# 19-EEPROM_PRESENCE_DETECTION_TEMP_SENSOR.net
KiCad netlist of a schematic drawn in Altium Designer
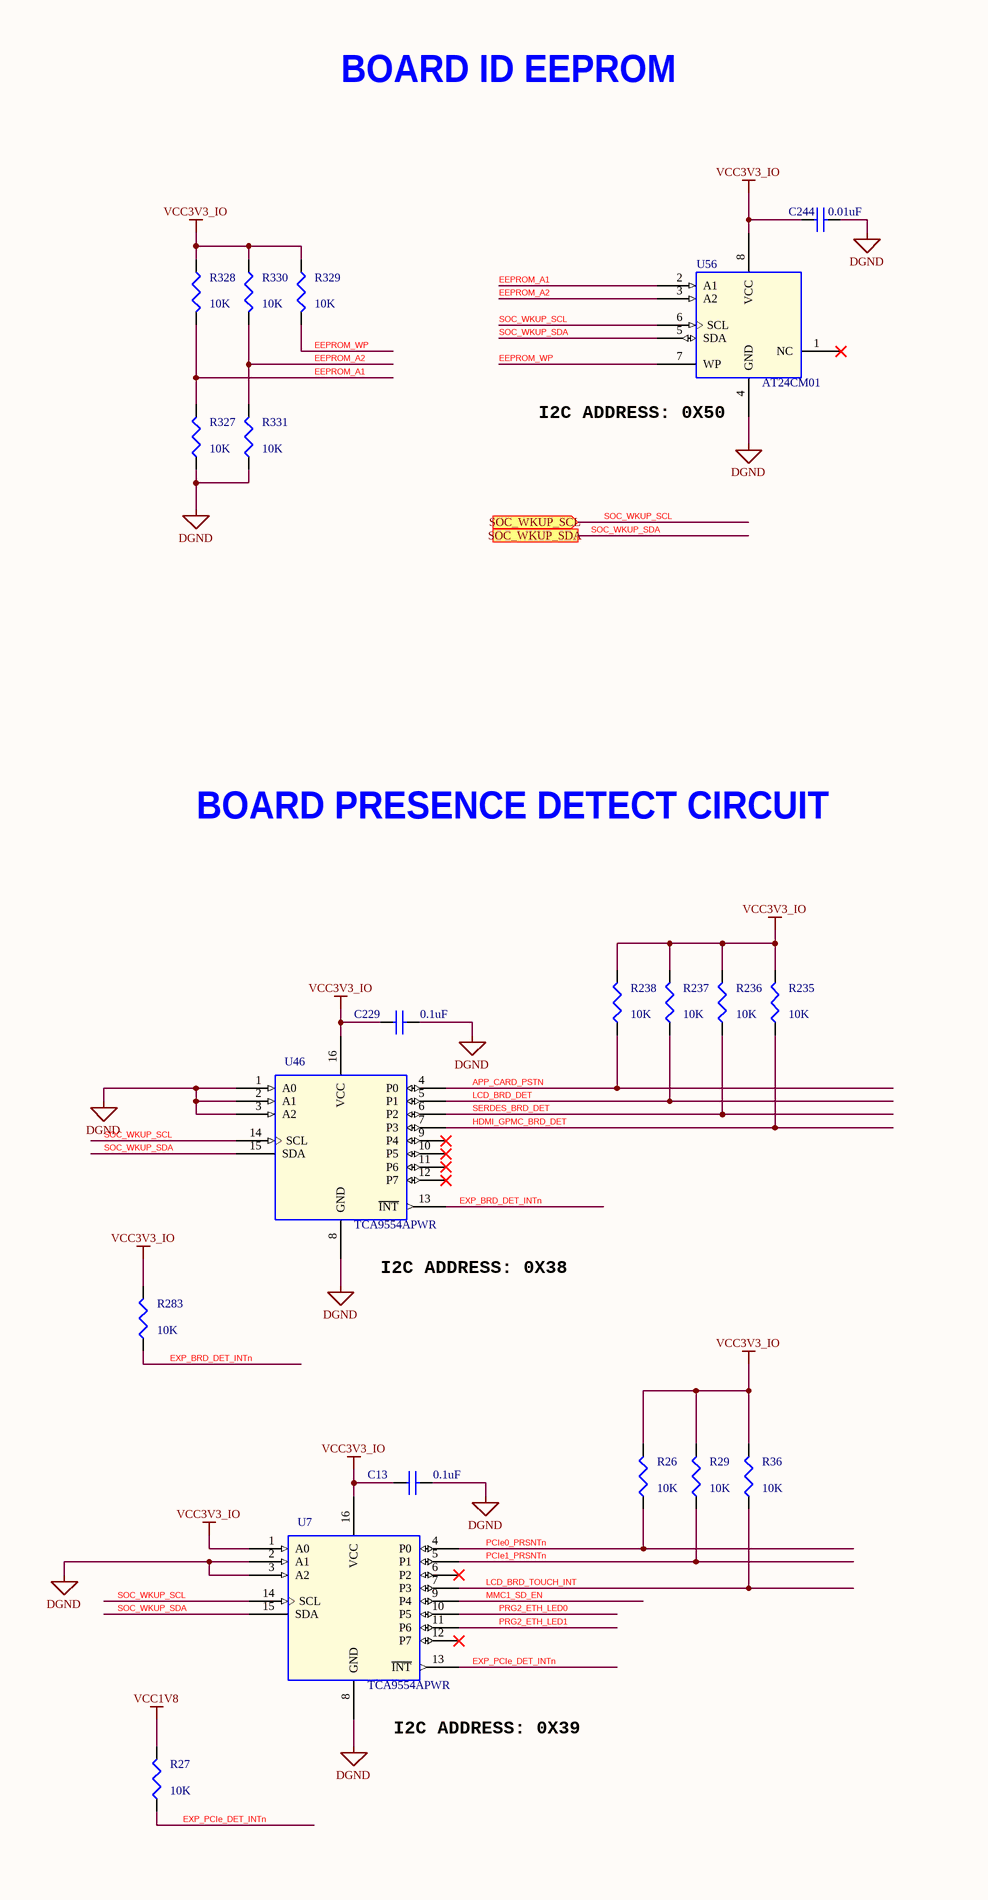
[diagram p0: 19-EEPROM,PRESENCE DETECTION & TEMP SENSOR.SchDoc, left]
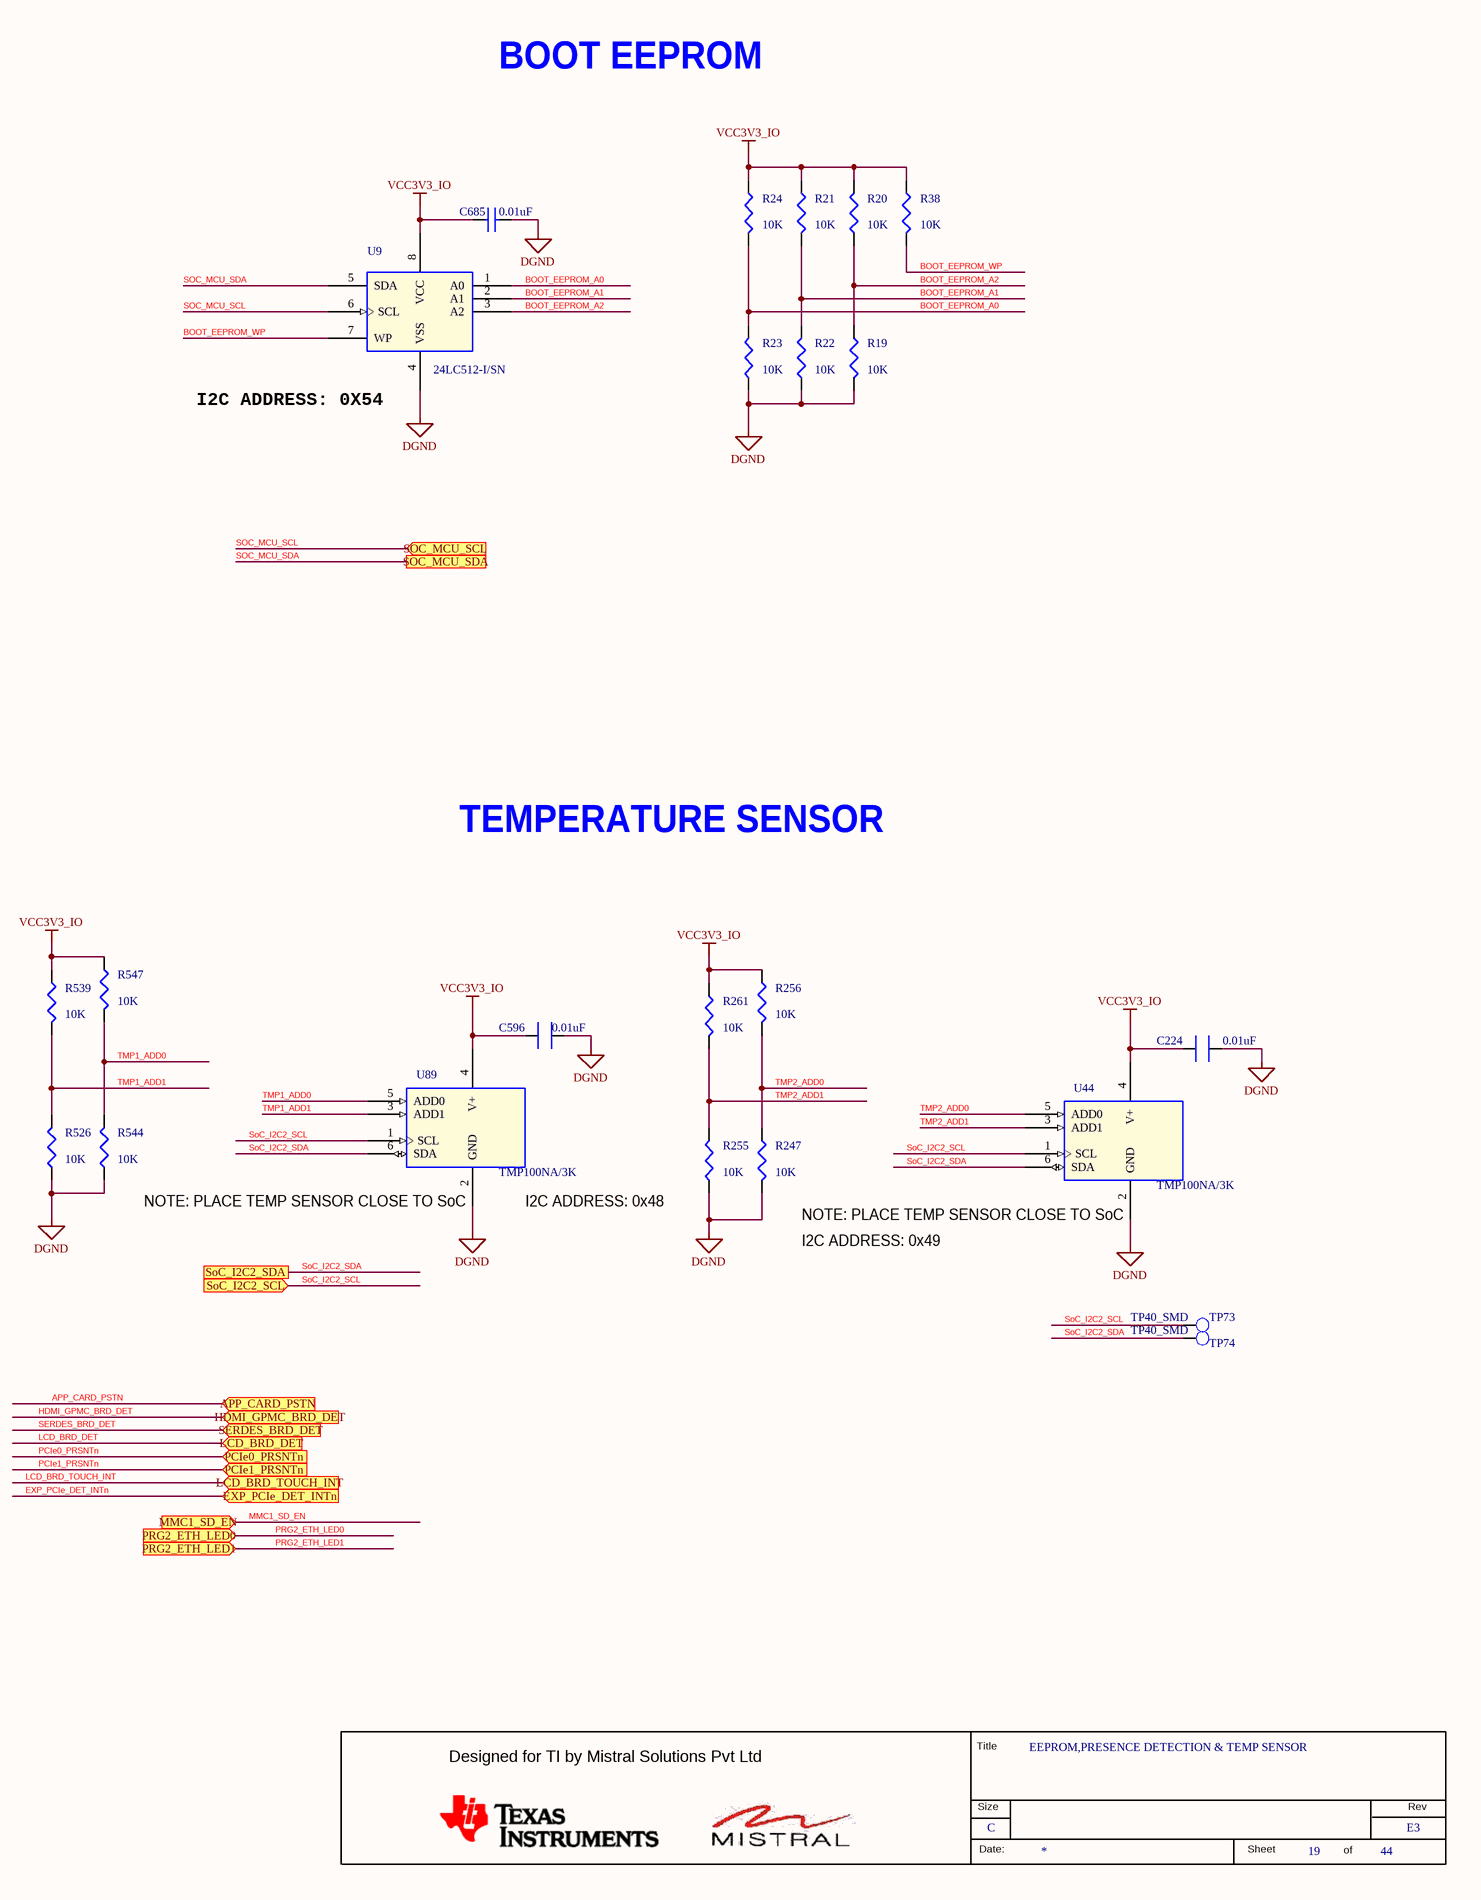
[diagram p1: 19-EEPROM,PRESENCE DETECTION & TEMP SENSOR.SchDoc, right]

(export (version "E")
  (design (tool "Eeschema 10.0.6"))
  (components
    (comp (ref "C13")
      (value "0.1uF")
      (footprint "CAP0201_0-5")
      (description "CAP CERAMIC 0.1uF 16V 10% X5R 0201")
      (fields (field (name "DISTRIBUTOR_PART_NUMBER") "490-16742-1-ND") (field (name "VOLTAGE") "16V"))
      (libsource (lib "*") (part "CAP_Dup5"))
    )
    (comp (ref "C224")
      (value "0.01uF")
      (footprint "TMDX654GPEVM_BRD:CAP0201_0-5")
      (description "CAP CERAMIC 0.01uF 25V 10% X5R 0201")
      (fields
        (field (name "MISTRAL PART NO") "120018010007-R")
        (field (name "MFR_PART_NUMBER") "GRM033R61E103KA12J")
      )
      (libsource (lib "*") (part "CAP_Dup3"))
    )
    (comp (ref "C229")
      (value "0.1uF")
      (footprint "CAP0201_0-5")
      (description "CAP CERAMIC 0.1uF 16V 10% X5R 0201")
      (fields (field (name "DISTRIBUTOR_PART_NUMBER") "490-16742-1-ND") (field (name "VOLTAGE") "16V"))
      (libsource (lib "*") (part "CAP_Dup5"))
    )
    (comp (ref "C244")
      (value "0.01uF")
      (footprint "CAP0201_0-5")
      (description "CAP CERAMIC 0.01uF 25V 10% X5R 0201")
      (fields
        (field (name "MISTRAL PART NO") "120018010007-R")
        (field (name "MFR_PART_NUMBER") "GRM033R61E103KA12J")
      )
      (libsource (lib "*") (part "CAP_Dup5"))
    )
    (comp (ref "C596")
      (value "0.01uF")
      (footprint "TMDX654GPEVM_BRD:CAP0201_0-5")
      (description "CAP CERAMIC 0.01uF 25V 10% X5R 0201")
      (fields
        (field (name "MISTRAL PART NO") "120018010007-R")
        (field (name "MFR_PART_NUMBER") "GRM033R61E103KA12J")
      )
      (libsource (lib "*") (part "CAP_Dup3"))
    )
    (comp (ref "C685")
      (value "0.01uF")
      (footprint "CAP0201_0-5")
      (description "CAP CERAMIC 0.01uF 25V 10% X5R 0201")
      (fields
        (field (name "MISTRAL PART NO") "120018010007-R")
        (field (name "MFR_PART_NUMBER") "GRM033R61E103KA12J")
      )
      (libsource (lib "*") (part "CAP_Dup5"))
    )
    (comp (ref "R19")
      (value "10K")
      (footprint "RES0402_0-5")
      (description "RES 10K 1/16W 5% 0402")
      (fields
        (field (name "MISTRAL PART NO") "110009030208-R")
        (field (name "MFR_PART_NUMBER") "RC0402JR-0710KL")
      )
      (libsource (lib "*") (part "RESISTOR_Dup5"))
    )
    (comp (ref "R20")
      (value "10K")
      (footprint "RES0402_0-5")
      (description "RES 10K 1/16W 5% 0402")
      (fields (field (name "DISTRIBUTOR_PART_NUMBER") "311-10KJRCT-ND") (field (name "VOLTAGE") "NA"))
      (libsource (lib "*") (part "RESISTOR_Dup5"))
    )
    (comp (ref "R21")
      (value "10K")
      (footprint "RES0402_0-5")
      (description "RES 10K 1/16W 5% 0402")
      (fields (field (name "DISTRIBUTOR_PART_NUMBER") "311-10KJRCT-ND") (field (name "VOLTAGE") "NA"))
      (libsource (lib "*") (part "RESISTOR_Dup5"))
    )
    (comp (ref "R22")
      (value "10K")
      (footprint "RES0402_0-5")
      (description "RES 10K 1/16W 5% 0402")
      (fields
        (field (name "MISTRAL PART NO") "110009030208-R")
        (field (name "MFR_PART_NUMBER") "RC0402JR-0710KL")
      )
      (libsource (lib "*") (part "RESISTOR_Dup5"))
    )
    (comp (ref "R23")
      (value "10K")
      (footprint "RES0402_0-5")
      (description "RES 10K 1/16W 5% 0402")
      (fields (field (name "DISTRIBUTOR_PART_NUMBER") "311-10KJRCT-ND") (field (name "VOLTAGE") "NA"))
      (libsource (lib "*") (part "RESISTOR_Dup5"))
    )
    (comp (ref "R24")
      (value "10K")
      (footprint "RES0402_0-5")
      (description "RES 10K 1/16W 5% 0402")
      (fields
        (field (name "MISTRAL PART NO") "110009030208-R")
        (field (name "MFR_PART_NUMBER") "RC0402JR-0710KL")
      )
      (libsource (lib "*") (part "RESISTOR_Dup5"))
    )
    (comp (ref "R26")
      (value "10K")
      (footprint "RES0402_0-5")
      (description "RES 10K 1/16W 5% 0402")
      (fields (field (name "DISTRIBUTOR_PART_NUMBER") "311-10KJRCT-ND") (field (name "VOLTAGE") "NA"))
      (libsource (lib "*") (part "RESISTOR_Dup5"))
    )
    (comp (ref "R27")
      (value "10K")
      (footprint "RES0402_0-5")
      (description "RES 10K 1/16W 5% 0402")
      (fields
        (field (name "MISTRAL PART NO") "110009030208-R")
        (field (name "MFR_PART_NUMBER") "RC0402JR-0710KL")
      )
      (libsource (lib "*") (part "RESISTOR_Dup5"))
    )
    (comp (ref "R29")
      (value "10K")
      (footprint "RES0402_0-5")
      (description "RES 10K 1/16W 5% 0402")
      (fields
        (field (name "MISTRAL PART NO") "110009030208-R")
        (field (name "MFR_PART_NUMBER") "RC0402JR-0710KL")
      )
      (libsource (lib "*") (part "RESISTOR_Dup5"))
    )
    (comp (ref "R36")
      (value "10K")
      (footprint "RES0402_0-5")
      (description "RES 10K 1/16W 5% 0402")
      (fields
        (field (name "MISTRAL PART NO") "110009030208-R")
        (field (name "MFR_PART_NUMBER") "RC0402JR-0710KL")
      )
      (libsource (lib "*") (part "RESISTOR_Dup5"))
    )
    (comp (ref "R38")
      (value "10K")
      (footprint "RES0402_0-5")
      (description "RES 10K 1/16W 5% 0402")
      (fields (field (name "DISTRIBUTOR_PART_NUMBER") "311-10KJRCT-ND") (field (name "VOLTAGE") "NA"))
      (libsource (lib "*") (part "RESISTOR_Dup5"))
    )
    (comp (ref "R235")
      (value "10K")
      (footprint "RES0402_0-5")
      (description "RES 10K 1/16W 5% 0402")
      (fields
        (field (name "MISTRAL PART NO") "110009030208-R")
        (field (name "MFR_PART_NUMBER") "RC0402JR-0710KL")
      )
      (libsource (lib "*") (part "RESISTOR_Dup5"))
    )
    (comp (ref "R236")
      (value "10K")
      (footprint "RES0402_0-5")
      (description "RES 10K 1/16W 5% 0402")
      (fields (field (name "DISTRIBUTOR_PART_NUMBER") "311-10KJRCT-ND") (field (name "VOLTAGE") "NA"))
      (libsource (lib "*") (part "RESISTOR_Dup5"))
    )
    (comp (ref "R237")
      (value "10K")
      (footprint "RES0402_0-5")
      (description "RES 10K 1/16W 5% 0402")
      (fields
        (field (name "MISTRAL PART NO") "110009030208-R")
        (field (name "MFR_PART_NUMBER") "RC0402JR-0710KL")
      )
      (libsource (lib "*") (part "RESISTOR_Dup5"))
    )
    (comp (ref "R238")
      (value "10K")
      (footprint "RES0402_0-5")
      (description "RES 10K 1/16W 5% 0402")
      (fields (field (name "DISTRIBUTOR_PART_NUMBER") "311-10KJRCT-ND") (field (name "VOLTAGE") "NA"))
      (libsource (lib "*") (part "RESISTOR_Dup5"))
    )
    (comp (ref "R247")
      (value "10K")
      (footprint "RES0402_0-5")
      (description "RES 10K 1/16W 5% 0402")
      (fields
        (field (name "MISTRAL PART NO") "110009030208-R")
        (field (name "MFR_PART_NUMBER") "RC0402JR-0710KL")
      )
      (libsource (lib "*") (part "RESISTOR_Dup5"))
    )
    (comp (ref "R255")
      (value "10K")
      (footprint "RES0402_0-5")
      (description "RES 10K 1/16W 5% 0402")
      (fields
        (field (name "MISTRAL PART NO") "110009030208-R")
        (field (name "MFR_PART_NUMBER") "RC0402JR-0710KL")
      )
      (libsource (lib "*") (part "RESISTOR_Dup5"))
    )
    (comp (ref "R256")
      (value "10K")
      (footprint "RES0402_0-5")
      (description "RES 10K 1/16W 5% 0402")
      (fields (field (name "DISTRIBUTOR_PART_NUMBER") "311-10KJRCT-ND") (field (name "VOLTAGE") "NA"))
      (libsource (lib "*") (part "RESISTOR_Dup5"))
    )
    (comp (ref "R261")
      (value "10K")
      (footprint "RES0402_0-5")
      (description "RES 10K 1/16W 5% 0402")
      (fields (field (name "DISTRIBUTOR_PART_NUMBER") "311-10KJRCT-ND") (field (name "VOLTAGE") "NA"))
      (libsource (lib "*") (part "RESISTOR_Dup5"))
    )
    (comp (ref "R283")
      (value "10K")
      (footprint "RES0402_0-5")
      (description "RES 10K 1/16W 5% 0402")
      (fields
        (field (name "MISTRAL PART NO") "110009030208-R")
        (field (name "MFR_PART_NUMBER") "RC0402JR-0710KL")
      )
      (libsource (lib "*") (part "RESISTOR_Dup5"))
    )
    (comp (ref "R327")
      (value "10K")
      (footprint "RES0402_0-5")
      (description "RES 10K 1/16W 5% 0402")
      (fields
        (field (name "MISTRAL PART NO") "110009030208-R")
        (field (name "MFR_PART_NUMBER") "RC0402JR-0710KL")
      )
      (libsource (lib "*") (part "RESISTOR_Dup5"))
    )
    (comp (ref "R328")
      (value "10K")
      (footprint "RES0402_0-5")
      (description "RES 10K 1/16W 5% 0402")
      (fields (field (name "DISTRIBUTOR_PART_NUMBER") "311-10KJRCT-ND") (field (name "VOLTAGE") "NA"))
      (libsource (lib "*") (part "RESISTOR_Dup5"))
    )
    (comp (ref "R329")
      (value "10K")
      (footprint "RES0402_0-5")
      (description "RES 10K 1/16W 5% 0402")
      (fields (field (name "DISTRIBUTOR_PART_NUMBER") "311-10KJRCT-ND") (field (name "VOLTAGE") "NA"))
      (libsource (lib "*") (part "RESISTOR_Dup5"))
    )
    (comp (ref "R330")
      (value "10K")
      (footprint "RES0402_0-5")
      (description "RES 10K 1/16W 5% 0402")
      (fields
        (field (name "MISTRAL PART NO") "110009030208-R")
        (field (name "MFR_PART_NUMBER") "RC0402JR-0710KL")
      )
      (libsource (lib "*") (part "RESISTOR_Dup5"))
    )
    (comp (ref "R331")
      (value "10K")
      (footprint "RES0402_0-5")
      (description "RES 10K 1/16W 5% 0402")
      (fields (field (name "DISTRIBUTOR_PART_NUMBER") "311-10KJRCT-ND") (field (name "VOLTAGE") "NA"))
      (libsource (lib "*") (part "RESISTOR_Dup5"))
    )
    (comp (ref "R526")
      (value "10K")
      (footprint "RES0402_0-5")
      (description "RES 10K 1/16W 5% 0402")
      (fields (field (name "DISTRIBUTOR_PART_NUMBER") "311-10KJRCT-ND") (field (name "VOLTAGE") "NA"))
      (libsource (lib "*") (part "RESISTOR_Dup5"))
    )
    (comp (ref "R539")
      (value "10K")
      (footprint "RES0402_0-5")
      (description "RES 10K 1/16W 5% 0402")
      (fields
        (field (name "MISTRAL PART NO") "110009030208-R")
        (field (name "MFR_PART_NUMBER") "RC0402JR-0710KL")
      )
      (libsource (lib "*") (part "RESISTOR_Dup5"))
    )
    (comp (ref "R544")
      (value "10K")
      (footprint "RES0402_0-5")
      (description "RES 10K 1/16W 5% 0402")
      (fields
        (field (name "MISTRAL PART NO") "110009030208-R")
        (field (name "MFR_PART_NUMBER") "RC0402JR-0710KL")
      )
      (libsource (lib "*") (part "RESISTOR_Dup5"))
    )
    (comp (ref "R547")
      (value "10K")
      (footprint "RES0402_0-5")
      (description "RES 10K 1/16W 5% 0402")
      (fields
        (field (name "MISTRAL PART NO") "110009030208-R")
        (field (name "MFR_PART_NUMBER") "RC0402JR-0710KL")
      )
      (libsource (lib "*") (part "RESISTOR_Dup5"))
    )
    (comp (ref "TP73")
      (value "TP40_SMD")
      (footprint "TP40_SMD")
      (description "TESTPOINT CIR 40 SMD")
      (fields (field (name "VOLTAGE") "NA") (field (name "MISTRAL PART NO") "130009030933"))
      (libsource (lib "*") (part "TESTPOINT"))
    )
    (comp (ref "TP74")
      (value "TP40_SMD")
      (footprint "TP40_SMD")
      (description "TESTPOINT CIR 40 SMD")
      (fields (field (name "MISTRAL PART NO") "130009030933") (field (name "DISTRIBUTOR_PART_NUMBER") "NA"))
      (libsource (lib "*") (part "TESTPOINT"))
    )
    (comp (ref "U7")
      (value "TCA9554APWR")
      (footprint "TSSOP16_25-59_205X180_1-2")
      (description "IC 8-BIT I2C AND SMBUS I/O EXPANDER WITH INTERRUPT O/P TSSOP16")
      (fields (field (name "MISTRAL PART NO") "141017090007-R") (field (name "TOLERANCE") "NA"))
      (libsource (lib "*") (part "TCA9554APWR_TSSOP16"))
    )
    (comp (ref "U9")
      (value "24LC512-I/SN")
      (footprint "SOIC8_1-8")
      (description "IC 512K I2C SERIAL EEPROM MEMORY SOIC8")
      (fields (field (name "MISTRAL PART NO") "141117080005-R") (field (name "TOLERANCE") "NA"))
      (libsource (lib "*") (part "24LC512-ESN_SOIC8"))
    )
    (comp (ref "U44")
      (value "TMP100NA/3K")
      (footprint "SOT23-6_1-5")
      (description "IC TEMPERATURE SENSOR WITH I2C AND SMBUS INTERFACE SOT23-6")
      (fields (field (name "DISTRIBUTOR_PART_NUMBER") "296-26833-1-ND") (field (name "VOLTAGE") "NA"))
      (libsource (lib "*") (part "TMP100NA/3K_SOT23-6"))
    )
    (comp (ref "U46")
      (value "TCA9554APWR")
      (footprint "TSSOP16_25-59_205X180_1-2")
      (description "IC 8-BIT I2C AND SMBUS I/O EXPANDER WITH INTERRUPT O/P TSSOP16")
      (fields (field (name "MISTRAL PART NO") "141017090007-R") (field (name "TOLERANCE") "NA"))
      (libsource (lib "*") (part "TCA9554APWR_TSSOP16"))
    )
    (comp (ref "U56")
      (value "AT24CM01")
      (footprint "TSSOP8_25-59_125X180_1-2")
      (description "IC 1MBIT I2C SERIAL EEPROM TSSOP8")
      (fields
        (field (name "MISTRAL PART NO") "141114090006-R")
        (field (name "MFR_PART_NUMBER") "AT24CM01-XHD-T")
      )
      (libsource (lib "*") (part "AT24HC04B-TH-B_TSSOP8"))
    )
    (comp (ref "U89")
      (value "TMP100NA/3K")
      (footprint "SOT23-6_1-5")
      (description "IC TEMPERATURE SENSOR WITH I2C AND SMBUS INTERFACE SOT23-6")
      (fields (field (name "MISTRAL PART NO") "141017080030-R") (field (name "TOLERANCE") "NA"))
      (libsource (lib "*") (part "TMP100NA/3K_SOT23-6"))
    )
  )
  (nets
    (net (code "1") (name "/APP_CARD_PSTN") (class "Default")
      (node (ref "R238") (pin "1") (pinfunction "1_1") (pintype "passive"))
      (node (ref "U46") (pin "4") (pinfunction "P0_4") (pintype "bidirectional"))
    )
    (net (code "2") (name "/BOOT_EEPROM_A0") (class "Default")
      (node (ref "R23") (pin "2") (pinfunction "2_2") (pintype "passive"))
      (node (ref "R24") (pin "2") (pinfunction "2_2") (pintype "passive"))
      (node (ref "U9") (pin "1") (pinfunction "A0_1") (pintype "passive"))
    )
    (net (code "3") (name "/BOOT_EEPROM_A1") (class "Default")
      (node (ref "R21") (pin "2") (pinfunction "2_2") (pintype "passive"))
      (node (ref "R22") (pin "2") (pinfunction "2_2") (pintype "passive"))
      (node (ref "U9") (pin "2") (pinfunction "A1_2") (pintype "passive"))
    )
    (net (code "4") (name "/BOOT_EEPROM_A2") (class "Default")
      (node (ref "R19") (pin "1") (pinfunction "1_1") (pintype "passive"))
      (node (ref "R20") (pin "1") (pinfunction "1_1") (pintype "passive"))
      (node (ref "U9") (pin "3") (pinfunction "A2_3") (pintype "passive"))
    )
    (net (code "5") (name "/BOOT_EEPROM_WP") (class "Default")
      (node (ref "R38") (pin "2") (pinfunction "2_2") (pintype "passive"))
      (node (ref "U9") (pin "7") (pinfunction "WP_7") (pintype "passive"))
    )
    (net (code "6") (name "/EEPROM_A1") (class "Default")
      (node (ref "R327") (pin "2") (pinfunction "2_2") (pintype "passive"))
      (node (ref "R328") (pin "2") (pinfunction "2_2") (pintype "passive"))
      (node (ref "U56") (pin "2") (pinfunction "A1_2") (pintype "input"))
    )
    (net (code "7") (name "/EEPROM_A2") (class "Default")
      (node (ref "R330") (pin "2") (pinfunction "2_2") (pintype "passive"))
      (node (ref "R331") (pin "2") (pinfunction "2_2") (pintype "passive"))
      (node (ref "U56") (pin "3") (pinfunction "A2_3") (pintype "input"))
    )
    (net (code "8") (name "/EEPROM_WP") (class "Default")
      (node (ref "R329") (pin "2") (pinfunction "2_2") (pintype "passive"))
      (node (ref "U56") (pin "7") (pinfunction "WP_7") (pintype "passive"))
    )
    (net (code "9") (name "/EXP_BRD_DET_INTn") (class "Default")
      (node (ref "R283") (pin "1") (pinfunction "1_1") (pintype "passive"))
      (node (ref "U46") (pin "13") (pinfunction "~{INT}_13") (pintype "output"))
    )
    (net (code "10") (name "/EXP_PCIe_DET_INTn") (class "Default")
      (node (ref "R27") (pin "1") (pinfunction "1_1") (pintype "passive"))
      (node (ref "U7") (pin "13") (pinfunction "~{INT}_13") (pintype "output"))
    )
    (net (code "11") (name "/HDMI_GPMC_BRD_DET") (class "Default")
      (node (ref "R235") (pin "1") (pinfunction "1_1") (pintype "passive"))
      (node (ref "U46") (pin "7") (pinfunction "P3_7") (pintype "bidirectional"))
    )
    (net (code "12") (name "/LCD_BRD_DET") (class "Default")
      (node (ref "R237") (pin "1") (pinfunction "1_1") (pintype "passive"))
      (node (ref "U46") (pin "5") (pinfunction "P1_5") (pintype "bidirectional"))
    )
    (net (code "13") (name "/LCD_BRD_TOUCH_INT") (class "Default")
      (node (ref "R36") (pin "1") (pinfunction "1_1") (pintype "passive"))
      (node (ref "U7") (pin "7") (pinfunction "P3_7") (pintype "bidirectional"))
    )
    (net (code "14") (name "/MMC1_SD_EN") (class "Default")
      (node (ref "U7") (pin "9") (pinfunction "P4_9") (pintype "bidirectional"))
    )
    (net (code "15") (name "/PCIe0_PRSNTn") (class "Default")
      (node (ref "R26") (pin "1") (pinfunction "1_1") (pintype "passive"))
      (node (ref "U7") (pin "4") (pinfunction "P0_4") (pintype "bidirectional"))
    )
    (net (code "16") (name "/PCIe1_PRSNTn") (class "Default")
      (node (ref "R29") (pin "1") (pinfunction "1_1") (pintype "passive"))
      (node (ref "U7") (pin "5") (pinfunction "P1_5") (pintype "bidirectional"))
    )
    (net (code "17") (name "/PRG2_ETH_LED0") (class "Default")
      (node (ref "U7") (pin "10") (pinfunction "P5_10") (pintype "bidirectional"))
    )
    (net (code "18") (name "/PRG2_ETH_LED1") (class "Default")
      (node (ref "U7") (pin "11") (pinfunction "P6_11") (pintype "bidirectional"))
    )
    (net (code "19") (name "/SERDES_BRD_DET") (class "Default")
      (node (ref "R236") (pin "1") (pinfunction "1_1") (pintype "passive"))
      (node (ref "U46") (pin "6") (pinfunction "P2_6") (pintype "bidirectional"))
    )
    (net (code "20") (name "/SOC_MCU_SCL") (class "Default")
      (node (ref "U9") (pin "6") (pinfunction "SCL_6") (pintype "input"))
    )
    (net (code "21") (name "/SOC_MCU_SDA") (class "Default")
      (node (ref "U9") (pin "5") (pinfunction "SDA_5") (pintype "passive"))
    )
    (net (code "22") (name "/SOC_WKUP_SCL") (class "Default")
      (node (ref "U46") (pin "14") (pinfunction "SCL_14") (pintype "input"))
      (node (ref "U56") (pin "6") (pinfunction "SCL_6") (pintype "input"))
      (node (ref "U7") (pin "14") (pinfunction "SCL_14") (pintype "input"))
    )
    (net (code "23") (name "/SOC_WKUP_SDA") (class "Default")
      (node (ref "U46") (pin "15") (pinfunction "SDA_15") (pintype "tri_state"))
      (node (ref "U56") (pin "5") (pinfunction "SDA_5") (pintype "bidirectional"))
      (node (ref "U7") (pin "15") (pinfunction "SDA_15") (pintype "tri_state"))
    )
    (net (code "24") (name "/SoC_I2C2_SCL") (class "Default")
      (node (ref "TP73") (pin "1") (pinfunction "TP_1") (pintype "passive"))
      (node (ref "U44") (pin "1") (pinfunction "SCL_1") (pintype "input"))
      (node (ref "U89") (pin "1") (pinfunction "SCL_1") (pintype "input"))
    )
    (net (code "25") (name "/SoC_I2C2_SDA") (class "Default")
      (node (ref "TP74") (pin "1") (pinfunction "TP_1") (pintype "passive"))
      (node (ref "U44") (pin "6") (pinfunction "SDA_6") (pintype "bidirectional"))
      (node (ref "U89") (pin "6") (pinfunction "SDA_6") (pintype "bidirectional"))
    )
    (net (code "26") (name "/TMP1_ADD0") (class "Default")
      (node (ref "R544") (pin "2") (pinfunction "2_2") (pintype "passive"))
      (node (ref "R547") (pin "2") (pinfunction "2_2") (pintype "passive"))
      (node (ref "U89") (pin "5") (pinfunction "ADD0_5") (pintype "input"))
    )
    (net (code "27") (name "/TMP1_ADD1") (class "Default")
      (node (ref "R526") (pin "2") (pinfunction "2_2") (pintype "passive"))
      (node (ref "R539") (pin "2") (pinfunction "2_2") (pintype "passive"))
      (node (ref "U89") (pin "3") (pinfunction "ADD1_3") (pintype "input"))
    )
    (net (code "28") (name "/TMP2_ADD0") (class "Default")
      (node (ref "R247") (pin "1") (pinfunction "1_1") (pintype "passive"))
      (node (ref "R256") (pin "2") (pinfunction "2_2") (pintype "passive"))
      (node (ref "U44") (pin "5") (pinfunction "ADD0_5") (pintype "input"))
    )
    (net (code "29") (name "/TMP2_ADD1") (class "Default")
      (node (ref "R255") (pin "2") (pinfunction "2_2") (pintype "passive"))
      (node (ref "R261") (pin "2") (pinfunction "2_2") (pintype "passive"))
      (node (ref "U44") (pin "3") (pinfunction "ADD1_3") (pintype "input"))
    )
    (net (code "30") (name "DGND") (class "Default")
      (node (ref "C13") (pin "2") (pinfunction "2_2") (pintype "passive"))
      (node (ref "C224") (pin "1") (pinfunction "1_1") (pintype "passive"))
      (node (ref "C229") (pin "2") (pinfunction "2_2") (pintype "passive"))
      (node (ref "C244") (pin "2") (pinfunction "2_2") (pintype "passive"))
      (node (ref "C596") (pin "1") (pinfunction "1_1") (pintype "passive"))
      (node (ref "C685") (pin "2") (pinfunction "2_2") (pintype "passive"))
      (node (ref "R19") (pin "2") (pinfunction "2_2") (pintype "passive"))
      (node (ref "R22") (pin "1") (pinfunction "1_1") (pintype "passive"))
      (node (ref "R23") (pin "1") (pinfunction "1_1") (pintype "passive"))
      (node (ref "R247") (pin "2") (pinfunction "2_2") (pintype "passive"))
      (node (ref "R255") (pin "1") (pinfunction "1_1") (pintype "passive"))
      (node (ref "R327") (pin "1") (pinfunction "1_1") (pintype "passive"))
      (node (ref "R331") (pin "1") (pinfunction "1_1") (pintype "passive"))
      (node (ref "R526") (pin "1") (pinfunction "1_1") (pintype "passive"))
      (node (ref "R544") (pin "1") (pinfunction "1_1") (pintype "passive"))
      (node (ref "U44") (pin "2") (pinfunction "GND_2") (pintype "power_in"))
      (node (ref "U46") (pin "1") (pinfunction "A0_1") (pintype "input"))
      (node (ref "U46") (pin "2") (pinfunction "A1_2") (pintype "input"))
      (node (ref "U46") (pin "3") (pinfunction "A2_3") (pintype "input"))
      (node (ref "U46") (pin "8") (pinfunction "GND_8") (pintype "power_in"))
      (node (ref "U56") (pin "4") (pinfunction "GND_4") (pintype "power_in"))
      (node (ref "U7") (pin "2") (pinfunction "A1_2") (pintype "input"))
      (node (ref "U7") (pin "3") (pinfunction "A2_3") (pintype "input"))
      (node (ref "U7") (pin "8") (pinfunction "GND_8") (pintype "power_in"))
      (node (ref "U89") (pin "2") (pinfunction "GND_2") (pintype "power_in"))
      (node (ref "U9") (pin "4") (pinfunction "VSS_4") (pintype "power_in"))
    )
    (net (code "31") (name "VCC1V8") (class "Default")
      (node (ref "R27") (pin "2") (pinfunction "2_2") (pintype "passive"))
    )
    (net (code "32") (name "VCC3V3_IO") (class "Default")
      (node (ref "C13") (pin "1") (pinfunction "1_1") (pintype "passive"))
      (node (ref "C224") (pin "2") (pinfunction "2_2") (pintype "passive"))
      (node (ref "C229") (pin "1") (pinfunction "1_1") (pintype "passive"))
      (node (ref "C244") (pin "1") (pinfunction "1_1") (pintype "passive"))
      (node (ref "C596") (pin "2") (pinfunction "2_2") (pintype "passive"))
      (node (ref "C685") (pin "1") (pinfunction "1_1") (pintype "passive"))
      (node (ref "R20") (pin "2") (pinfunction "2_2") (pintype "passive"))
      (node (ref "R21") (pin "1") (pinfunction "1_1") (pintype "passive"))
      (node (ref "R235") (pin "2") (pinfunction "2_2") (pintype "passive"))
      (node (ref "R236") (pin "2") (pinfunction "2_2") (pintype "passive"))
      (node (ref "R237") (pin "2") (pinfunction "2_2") (pintype "passive"))
      (node (ref "R238") (pin "2") (pinfunction "2_2") (pintype "passive"))
      (node (ref "R24") (pin "1") (pinfunction "1_1") (pintype "passive"))
      (node (ref "R256") (pin "1") (pinfunction "1_1") (pintype "passive"))
      (node (ref "R26") (pin "2") (pinfunction "2_2") (pintype "passive"))
      (node (ref "R261") (pin "1") (pinfunction "1_1") (pintype "passive"))
      (node (ref "R283") (pin "2") (pinfunction "2_2") (pintype "passive"))
      (node (ref "R29") (pin "2") (pinfunction "2_2") (pintype "passive"))
      (node (ref "R328") (pin "1") (pinfunction "1_1") (pintype "passive"))
      (node (ref "R329") (pin "1") (pinfunction "1_1") (pintype "passive"))
      (node (ref "R330") (pin "1") (pinfunction "1_1") (pintype "passive"))
      (node (ref "R36") (pin "2") (pinfunction "2_2") (pintype "passive"))
      (node (ref "R38") (pin "1") (pinfunction "1_1") (pintype "passive"))
      (node (ref "R539") (pin "1") (pinfunction "1_1") (pintype "passive"))
      (node (ref "R547") (pin "1") (pinfunction "1_1") (pintype "passive"))
      (node (ref "U44") (pin "4") (pinfunction "V+_4") (pintype "power_in"))
      (node (ref "U46") (pin "16") (pinfunction "VCC_16") (pintype "power_in"))
      (node (ref "U56") (pin "8") (pinfunction "VCC_8") (pintype "power_in"))
      (node (ref "U7") (pin "1") (pinfunction "A0_1") (pintype "input"))
      (node (ref "U7") (pin "16") (pinfunction "VCC_16") (pintype "power_in"))
      (node (ref "U89") (pin "4") (pinfunction "V+_4") (pintype "power_in"))
      (node (ref "U9") (pin "8") (pinfunction "VCC_8") (pintype "power_in"))
    )
    (net (code "33") (name "unconnected-(U7-P2-Pad6)") (class "Default")
      (node (ref "U7") (pin "6") (pinfunction "P2_6") (pintype "bidirectional+no_connect"))
    )
    (net (code "34") (name "unconnected-(U7-P7-Pad12)") (class "Default")
      (node (ref "U7") (pin "12") (pinfunction "P7_12") (pintype "bidirectional+no_connect"))
    )
    (net (code "35") (name "unconnected-(U46-P4-Pad9)") (class "Default")
      (node (ref "U46") (pin "9") (pinfunction "P4_9") (pintype "bidirectional+no_connect"))
    )
    (net (code "36") (name "unconnected-(U46-P5-Pad10)") (class "Default")
      (node (ref "U46") (pin "10") (pinfunction "P5_10") (pintype "bidirectional+no_connect"))
    )
    (net (code "37") (name "unconnected-(U46-P6-Pad11)") (class "Default")
      (node (ref "U46") (pin "11") (pinfunction "P6_11") (pintype "bidirectional+no_connect"))
    )
    (net (code "38") (name "unconnected-(U46-P7-Pad12)") (class "Default")
      (node (ref "U46") (pin "12") (pinfunction "P7_12") (pintype "bidirectional+no_connect"))
    )
    (net (code "39") (name "unconnected-(U56-NC-Pad1)") (class "Default")
      (node (ref "U56") (pin "1") (pinfunction "NC_1") (pintype "passive+no_connect"))
    )
  )
)
